# jetson_agx_breakout.net
KiCad netlist of a schematic drawn in Altium Designer
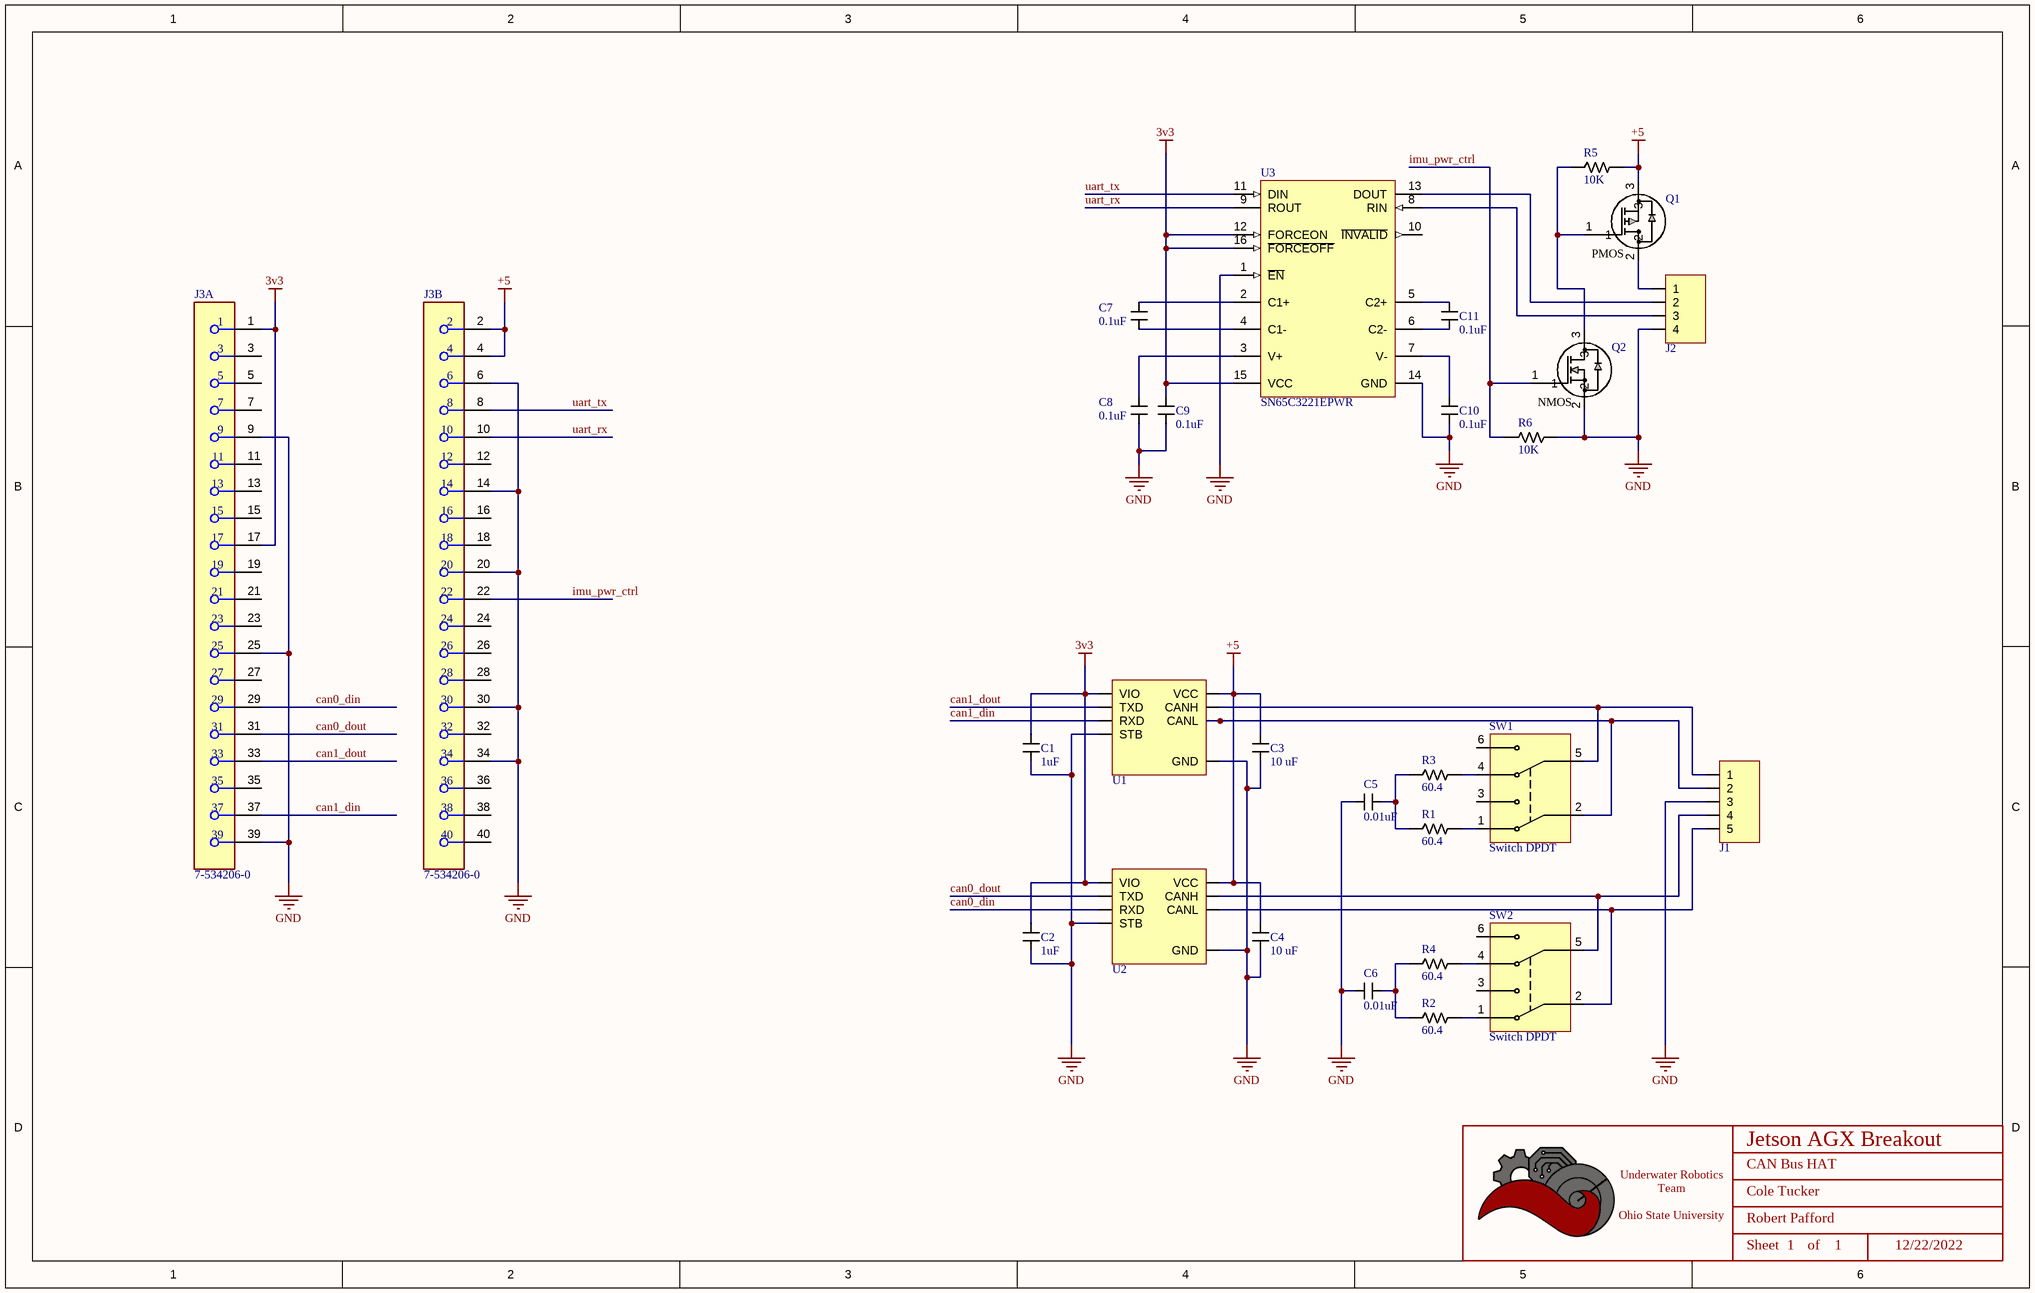
[diagram p0: jetson_agx_breakout.SchDoc]

(export (version "E")
  (design (tool "Eeschema 10.0.6"))
  (components
    (comp (ref "*")
      (value "Title_Block")
      (footprint "LOGO")
      (description "UWRT Schematic Title Block Template\r\n\r\nCreated June 2021, Dylan Trainor")
      (libsource (lib "UWRT") (part "Title_Block"))
    )
    (comp (ref "C1")
      (value "1uF")
      (footprint "CAPACITOR_0603")
      (description "Cap 1uF 16V +/-10%\r\nCeramic 0603")
      (fields
        (field (name "TOLERANCE") "+/- 10%")
        (field (name "VOLTAGE") "16V")
        (field (name "MADE BY") "Flip B")
      )
      (libsource (lib "Capacitors") (part "CAPACITOR_1uF_0603"))
    )
    (comp (ref "C2")
      (value "1uF")
      (footprint "CAPACITOR_0603")
      (description "Cap 1uF 16V +/-10%\r\nCeramic 0603")
      (fields
        (field (name "TOLERANCE") "+/- 10%")
        (field (name "VOLTAGE") "16V")
        (field (name "MADE BY") "Flip B")
      )
      (libsource (lib "Capacitors") (part "CAPACITOR_1uF_0603"))
    )
    (comp (ref "C3")
      (value "10uF Ceramic 6.3V")
      (footprint "CAPACITOR_0603")
      (description "Cap 10uF 6.3V +/-20%\r\nCeramic 0603")
      (fields
        (field (name "TOLERANCE") "+/- 20%")
        (field (name "VOLTAGE") "6.3V")
        (field (name "VALUE (UF)") "10 uF")
        (field (name "MADE BY") "Flip B")
      )
      (libsource (lib "Capacitors") (part "CAPACITOR_10uF_0603"))
    )
    (comp (ref "C4")
      (value "10uF Ceramic 6.3V")
      (footprint "CAPACITOR_0603")
      (description "Cap 10uF 6.3V +/-20%\r\nCeramic 0603")
      (fields
        (field (name "TOLERANCE") "+/- 20%")
        (field (name "VOLTAGE") "6.3V")
        (field (name "VALUE (UF)") "10 uF")
        (field (name "MADE BY") "Flip B")
      )
      (libsource (lib "Capacitors") (part "CAPACITOR_10uF_0603"))
    )
    (comp (ref "C5")
      (value "0.01uF")
      (footprint "CAPACITOR_0603")
      (description "Cap 10nF 6.3V +/-20%\r\nCeramic 0603")
      (fields
        (field (name "TOLERANCE") "+/- 10%")
        (field (name "VOLTAGE") "6.3V")
        (field (name "MADE BY") "Flip B")
      )
      (libsource (lib "Capacitors") (part "CAPACITOR_0.01uF_0603"))
    )
    (comp (ref "C6")
      (value "0.01uF")
      (footprint "CAPACITOR_0603")
      (description "Cap 10nF 6.3V +/-20%\r\nCeramic 0603")
      (fields
        (field (name "TOLERANCE") "+/- 10%")
        (field (name "VOLTAGE") "6.3V")
        (field (name "MADE BY") "Flip B")
      )
      (libsource (lib "Capacitors") (part "CAPACITOR_0.01uF_0603"))
    )
    (comp (ref "C7")
      (value "0.1uF")
      (footprint "CAPACITOR_0603")
      (description "Cap 100nF 6.3V +/-10%\r\nCeramic 0603")
      (fields
        (field (name "TOLERANCE") "+/- 10%")
        (field (name "VOLTAGE") "6.3V")
        (field (name "MADE BY") "Flip B")
      )
      (libsource (lib "Capacitors") (part "CAPACITOR_0.1uF_0603"))
    )
    (comp (ref "C8")
      (value "0.1uF")
      (footprint "CAPACITOR_0603")
      (description "Cap 100nF 6.3V +/-10%\r\nCeramic 0603")
      (fields
        (field (name "TOLERANCE") "+/- 10%")
        (field (name "VOLTAGE") "6.3V")
        (field (name "MADE BY") "Flip B")
      )
      (libsource (lib "Capacitors") (part "CAPACITOR_0.1uF_0603"))
    )
    (comp (ref "C9")
      (value "0.1uF")
      (footprint "CAPACITOR_0603")
      (description "Cap 100nF 6.3V +/-10%\r\nCeramic 0603")
      (fields
        (field (name "TOLERANCE") "+/- 10%")
        (field (name "VOLTAGE") "6.3V")
        (field (name "MADE BY") "Flip B")
      )
      (libsource (lib "Capacitors") (part "CAPACITOR_0.1uF_0603"))
    )
    (comp (ref "C10")
      (value "0.1uF")
      (footprint "CAPACITOR_0603")
      (description "Cap 100nF 6.3V +/-10%\r\nCeramic 0603")
      (fields
        (field (name "TOLERANCE") "+/- 10%")
        (field (name "VOLTAGE") "6.3V")
        (field (name "MADE BY") "Flip B")
      )
      (libsource (lib "Capacitors") (part "CAPACITOR_0.1uF_0603"))
    )
    (comp (ref "C11")
      (value "0.1uF")
      (footprint "CAPACITOR_0603")
      (description "Cap 100nF 6.3V +/-10%\r\nCeramic 0603")
      (fields
        (field (name "TOLERANCE") "+/- 10%")
        (field (name "VOLTAGE") "6.3V")
        (field (name "MADE BY") "Flip B")
      )
      (libsource (lib "Capacitors") (part "CAPACITOR_0.1uF_0603"))
    )
    (comp (ref "J1")
      (value "5 POS VERT")
      (footprint "CONN_JST_XH254_5POS_VERT")
      (description "JST XH 2.54mm Pitch 5 Pos Vertical")
      (fields (field (name "MANUFACTURER") "JST") (field (name "CREATED BY") "Robert P"))
      (libsource (lib "Connectors") (part "CONN_JST_XH254_5POS_VERT"))
    )
    (comp (ref "J2")
      (value "4 POS VERT")
      (footprint "CONN_JST_XH254_4POS_VERT")
      (description "JST XH 2.54mm Pitch 4 Pos Vertical")
      (fields (field (name "MANUFACTURER") "JST") (field (name "CREATED BY") "Robert P"))
      (libsource (lib "Connectors") (part "CONN_JST_XH254_4POS_VERT"))
    )
    (comp (ref "J3")
      (value "7-534206-0")
      (footprint "FP-7-534206-0-MFG")
      (description "CONN RCPT 40POS 0.1 GOLD PCB")
      (fields
        (field (name "MANUFACTURER") "TE Connectivity")
        (field (name "OCTOPART") "https://octopart.com/7-534206-0-te+connectivity-39516831")
      )
      (libsource (lib "Altium Content Vault") (part "7acf1c4a8db21028d11741a46a6ec78"))
    )
    (comp (ref "Q1")
      (value "MOSFET P-CHANNEL 20V 4.7A SOT23")
      (footprint "SOT-23-3")
      (description "P-Channel 20 V 4.7A (Tc) 1.56W (Tc) Surface Mount SOT-23")
      (fields
        (field (name "MANUFACTURER_PART_NUMBER") "TSM500P02CX")
        (field (name "CREATED BY") "Robert Pafford")
      )
      (libsource (lib "Transistors") (part "TSM500P02CX"))
    )
    (comp (ref "Q2")
      (value "MOSFET N-CH 30V 5.8A SOT-23-3")
      (footprint "SOT-23-3")
      (description "N-Channel 30 V 5.8A (Ta) 1.4W (Ta) Surface Mount SOT-23-3")
      (fields (field (name "MANUFACTURER _PART_NUMBER") "AO3404A") (field (name "CREATED BY") "Dylan T"))
      (libsource (lib "Transistors") (part "AO3404A"))
    )
    (comp (ref "R1")
      (value "60.4 Ohm 1% 1/16W")
      (footprint "RESISTOR_0402")
      (description "RES 60.4 OHM 1% 1/16W 0402")
      (fields
        (field (name "TOLERANCE") "+/- 1%")
        (field (name "VALUE  (OHMS)") "60.4")
        (field (name "MADE BY") "Robert Pafford")
      )
      (libsource (lib "Resistors") (part "RESISTOR_60.4_0402"))
    )
    (comp (ref "R2")
      (value "60.4 Ohm 1% 1/16W")
      (footprint "RESISTOR_0402")
      (description "RES 60.4 OHM 1% 1/16W 0402")
      (fields
        (field (name "TOLERANCE") "+/- 1%")
        (field (name "VALUE  (OHMS)") "60.4")
        (field (name "MADE BY") "Robert Pafford")
      )
      (libsource (lib "Resistors") (part "RESISTOR_60.4_0402"))
    )
    (comp (ref "R3")
      (value "60.4 Ohm 1% 1/16W")
      (footprint "RESISTOR_0402")
      (description "RES 60.4 OHM 1% 1/16W 0402")
      (fields
        (field (name "TOLERANCE") "+/- 1%")
        (field (name "VALUE  (OHMS)") "60.4")
        (field (name "MADE BY") "Robert Pafford")
      )
      (libsource (lib "Resistors") (part "RESISTOR_60.4_0402"))
    )
    (comp (ref "R4")
      (value "60.4 Ohm 1% 1/16W")
      (footprint "RESISTOR_0402")
      (description "RES 60.4 OHM 1% 1/16W 0402")
      (fields
        (field (name "TOLERANCE") "+/- 1%")
        (field (name "VALUE  (OHMS)") "60.4")
        (field (name "MADE BY") "Robert Pafford")
      )
      (libsource (lib "Resistors") (part "RESISTOR_60.4_0402"))
    )
    (comp (ref "R5")
      (value "10k Ohm 5% 1/10W")
      (footprint "RESISTOR_0603")
      (description "RES 10k OHM 5% 1/10W 0603")
      (fields
        (field (name "TOLERANCE") "+/- 5%")
        (field (name "VALUE  (OHMS)") "10K")
        (field (name "MADE BY") "Robert Pafford")
      )
      (libsource (lib "Resistors") (part "RESISTOR_10K_0603"))
    )
    (comp (ref "R6")
      (value "10k Ohm 5% 1/10W")
      (footprint "RESISTOR_0603")
      (description "RES 10k OHM 5% 1/10W 0603")
      (fields
        (field (name "TOLERANCE") "+/- 5%")
        (field (name "VALUE  (OHMS)") "10K")
        (field (name "MADE BY") "Robert Pafford")
      )
      (libsource (lib "Resistors") (part "RESISTOR_10K_0603"))
    )
    (comp (ref "SW1")
      (value "Switch DPDT")
      (footprint "CAS-220TA")
      (description "GOLD SWITCH FLUSH SLIDE DPDT 100MA 6V")
      (fields (field (name "MADE BY") "Robert Pafford"))
      (libsource (lib "Switches") (part "CAS-220TA_CAN_TERM"))
    )
    (comp (ref "SW2")
      (value "Switch DPDT")
      (footprint "CAS-220TA")
      (description "GOLD SWITCH FLUSH SLIDE DPDT 100MA 6V")
      (fields (field (name "MADE BY") "Robert Pafford"))
      (libsource (lib "Switches") (part "CAS-220TA_CAN_TERM"))
    )
    (comp (ref "U1")
      (value "CAN Transceiver")
      (footprint "SOIC-8")
      (description "CAN Interface IC High-Speed CAN Transceiver with Standby Mode")
      (fields (field (name "MADE BY") "Robert Pafford"))
      (libsource (lib "Integrated Circuits") (part "TJA1442AT"))
    )
    (comp (ref "U2")
      (value "CAN Transceiver")
      (footprint "SOIC-8")
      (description "CAN Interface IC High-Speed CAN Transceiver with Standby Mode")
      (fields (field (name "MADE BY") "Robert Pafford"))
      (libsource (lib "Integrated Circuits") (part "TJA1442AT"))
    )
    (comp (ref "U3")
      (value "SN65C3221EPWR")
      (footprint "PW0016A_M")
      (libsource (lib "Altium Content Vault") (part "TI-SN65C3221E-TSSOP_PW-16"))
    )
  )
  (nets
    (net (code "1") (name "+5") (class "Default")
      (node (ref "C3") (pin "1") (pinfunction "1_1") (pintype "passive"))
      (node (ref "C4") (pin "1") (pinfunction "1_1") (pintype "passive"))
      (node (ref "J3") (pin "2") (pinfunction "2_2") (pintype "passive"))
      (node (ref "J3") (pin "4") (pinfunction "4_4") (pintype "passive"))
      (node (ref "Q1") (pin "3") (pinfunction "3_3") (pintype "passive"))
      (node (ref "R5") (pin "1") (pinfunction "1_1") (pintype "passive"))
      (node (ref "U1") (pin "3") (pinfunction "VCC_3") (pintype "passive"))
      (node (ref "U2") (pin "3") (pinfunction "VCC_3") (pintype "passive"))
    )
    (net (code "2") (name "/can0_din") (class "Default")
      (node (ref "J3") (pin "29") (pinfunction "29_29") (pintype "passive"))
      (node (ref "U2") (pin "4") (pinfunction "RXD_4") (pintype "passive"))
    )
    (net (code "3") (name "/can0_dout") (class "Default")
      (node (ref "J3") (pin "31") (pinfunction "31_31") (pintype "passive"))
      (node (ref "U2") (pin "1") (pinfunction "TXD_1") (pintype "passive"))
    )
    (net (code "4") (name "/can1_din") (class "Default")
      (node (ref "J3") (pin "37") (pinfunction "37_37") (pintype "passive"))
      (node (ref "U1") (pin "4") (pinfunction "RXD_4") (pintype "passive"))
    )
    (net (code "5") (name "/can1_dout") (class "Default")
      (node (ref "J3") (pin "33") (pinfunction "33_33") (pintype "passive"))
      (node (ref "U1") (pin "1") (pinfunction "TXD_1") (pintype "passive"))
    )
    (net (code "6") (name "/imu_pwr_ctrl") (class "Default")
      (node (ref "J3") (pin "22") (pinfunction "22_22") (pintype "passive"))
      (node (ref "Q2") (pin "1") (pinfunction "1_1") (pintype "passive"))
      (node (ref "R6") (pin "1") (pinfunction "1_1") (pintype "passive"))
    )
    (net (code "7") (name "/uart_rx") (class "Default")
      (node (ref "J3") (pin "10") (pinfunction "10_10") (pintype "passive"))
      (node (ref "U3") (pin "9") (pinfunction "ROUT_9") (pintype "tri_state"))
    )
    (net (code "8") (name "/uart_tx") (class "Default")
      (node (ref "J3") (pin "8") (pinfunction "8_8") (pintype "passive"))
      (node (ref "U3") (pin "11") (pinfunction "DIN_11") (pintype "input"))
    )
    (net (code "9") (name "3v3") (class "Default")
      (node (ref "C1") (pin "1") (pinfunction "1_1") (pintype "passive"))
      (node (ref "C2") (pin "1") (pinfunction "1_1") (pintype "passive"))
      (node (ref "C9") (pin "1") (pinfunction "1_1") (pintype "passive"))
      (node (ref "J3") (pin "1") (pinfunction "1_1") (pintype "passive"))
      (node (ref "J3") (pin "17") (pinfunction "17_17") (pintype "passive"))
      (node (ref "U1") (pin "5") (pinfunction "VIO_5") (pintype "passive"))
      (node (ref "U2") (pin "5") (pinfunction "VIO_5") (pintype "passive"))
      (node (ref "U3") (pin "12") (pinfunction "FORCEON_12") (pintype "input"))
      (node (ref "U3") (pin "15") (pinfunction "VCC_15") (pintype "power_in"))
      (node (ref "U3") (pin "16") (pinfunction "~{FORCEOFF}_16") (pintype "input"))
    )
    (net (code "10") (name "GND") (class "Default")
      (node (ref "C1") (pin "2") (pinfunction "2_2") (pintype "passive"))
      (node (ref "C10") (pin "2") (pinfunction "2_2") (pintype "passive"))
      (node (ref "C2") (pin "2") (pinfunction "2_2") (pintype "passive"))
      (node (ref "C3") (pin "2") (pinfunction "2_2") (pintype "passive"))
      (node (ref "C4") (pin "2") (pinfunction "2_2") (pintype "passive"))
      (node (ref "C5") (pin "1") (pinfunction "1_1") (pintype "passive"))
      (node (ref "C6") (pin "1") (pinfunction "1_1") (pintype "passive"))
      (node (ref "C8") (pin "2") (pinfunction "2_2") (pintype "passive"))
      (node (ref "C9") (pin "2") (pinfunction "2_2") (pintype "passive"))
      (node (ref "J1") (pin "3") (pinfunction "3_3") (pintype "passive"))
      (node (ref "J2") (pin "4") (pinfunction "4_4") (pintype "passive"))
      (node (ref "J3") (pin "14") (pinfunction "14_14") (pintype "passive"))
      (node (ref "J3") (pin "20") (pinfunction "20_20") (pintype "passive"))
      (node (ref "J3") (pin "25") (pinfunction "25_25") (pintype "passive"))
      (node (ref "J3") (pin "30") (pinfunction "30_30") (pintype "passive"))
      (node (ref "J3") (pin "34") (pinfunction "34_34") (pintype "passive"))
      (node (ref "J3") (pin "39") (pinfunction "39_39") (pintype "passive"))
      (node (ref "J3") (pin "6") (pinfunction "6_6") (pintype "passive"))
      (node (ref "J3") (pin "9") (pinfunction "9_9") (pintype "passive"))
      (node (ref "Q2") (pin "2") (pinfunction "2_2") (pintype "passive"))
      (node (ref "R6") (pin "2") (pinfunction "2_2") (pintype "passive"))
      (node (ref "U1") (pin "2") (pinfunction "GND_2") (pintype "passive"))
      (node (ref "U1") (pin "8") (pinfunction "STB_8") (pintype "passive"))
      (node (ref "U2") (pin "2") (pinfunction "GND_2") (pintype "passive"))
      (node (ref "U2") (pin "8") (pinfunction "STB_8") (pintype "passive"))
      (node (ref "U3") (pin "1") (pinfunction "~{EN}_1") (pintype "input"))
      (node (ref "U3") (pin "14") (pinfunction "GND_14") (pintype "power_in"))
    )
    (net (code "11") (name "Net-(C5-Pad2)") (class "Default")
      (node (ref "C5") (pin "2") (pinfunction "2_2") (pintype "passive"))
      (node (ref "R1") (pin "2") (pinfunction "2_2") (pintype "passive"))
      (node (ref "R3") (pin "2") (pinfunction "2_2") (pintype "passive"))
    )
    (net (code "12") (name "Net-(C6-Pad2)") (class "Default")
      (node (ref "C6") (pin "2") (pinfunction "2_2") (pintype "passive"))
      (node (ref "R2") (pin "2") (pinfunction "2_2") (pintype "passive"))
      (node (ref "R4") (pin "2") (pinfunction "2_2") (pintype "passive"))
    )
    (net (code "13") (name "Net-(J2-Pad1)") (class "Default")
      (node (ref "J2") (pin "1") (pinfunction "1_1") (pintype "passive"))
      (node (ref "Q1") (pin "2") (pinfunction "2_2") (pintype "passive"))
    )
    (net (code "14") (name "Net-(Q1-Pad1)") (class "Default")
      (node (ref "Q1") (pin "1") (pinfunction "1_1") (pintype "passive"))
      (node (ref "Q2") (pin "3") (pinfunction "3_3") (pintype "passive"))
      (node (ref "R5") (pin "2") (pinfunction "2_2") (pintype "passive"))
    )
    (net (code "15") (name "Net-(R1-Pad1)") (class "Default")
      (node (ref "R1") (pin "1") (pinfunction "1_1") (pintype "passive"))
      (node (ref "SW1") (pin "1") (pintype "passive"))
    )
    (net (code "16") (name "Net-(R2-Pad1)") (class "Default")
      (node (ref "R2") (pin "1") (pinfunction "1_1") (pintype "passive"))
      (node (ref "SW2") (pin "1") (pintype "passive"))
    )
    (net (code "17") (name "Net-(R3-Pad1)") (class "Default")
      (node (ref "R3") (pin "1") (pinfunction "1_1") (pintype "passive"))
      (node (ref "SW1") (pin "4") (pintype "passive"))
    )
    (net (code "18") (name "Net-(R4-Pad1)") (class "Default")
      (node (ref "R4") (pin "1") (pinfunction "1_1") (pintype "passive"))
      (node (ref "SW2") (pin "4") (pintype "passive"))
    )
    (net (code "19") (name "Net-(U1-CANH)") (class "Default")
      (node (ref "J1") (pin "1") (pinfunction "1_1") (pintype "passive"))
      (node (ref "SW1") (pin "5") (pintype "passive"))
      (node (ref "U1") (pin "7") (pinfunction "CANH_7") (pintype "passive"))
    )
    (net (code "20") (name "Net-(U1-CANL)") (class "Default")
      (node (ref "J1") (pin "2") (pinfunction "2_2") (pintype "passive"))
      (node (ref "SW1") (pin "2") (pintype "passive"))
      (node (ref "U1") (pin "6") (pinfunction "CANL_6") (pintype "passive"))
    )
    (net (code "21") (name "Net-(U2-CANH)") (class "Default")
      (node (ref "J1") (pin "4") (pinfunction "4_4") (pintype "passive"))
      (node (ref "SW2") (pin "5") (pintype "passive"))
      (node (ref "U2") (pin "7") (pinfunction "CANH_7") (pintype "passive"))
    )
    (net (code "22") (name "Net-(U2-CANL)") (class "Default")
      (node (ref "J1") (pin "5") (pinfunction "5_5") (pintype "passive"))
      (node (ref "SW2") (pin "2") (pintype "passive"))
      (node (ref "U2") (pin "6") (pinfunction "CANL_6") (pintype "passive"))
    )
    (net (code "23") (name "Net-(U3-C1+)") (class "Default")
      (node (ref "C7") (pin "1") (pinfunction "1_1") (pintype "passive"))
      (node (ref "U3") (pin "2") (pinfunction "C1+_2") (pintype "passive"))
    )
    (net (code "24") (name "Net-(U3-C1-)") (class "Default")
      (node (ref "C7") (pin "2") (pinfunction "2_2") (pintype "passive"))
      (node (ref "U3") (pin "4") (pinfunction "C1-_4") (pintype "passive"))
    )
    (net (code "25") (name "Net-(U3-C2+)") (class "Default")
      (node (ref "C11") (pin "1") (pinfunction "1_1") (pintype "passive"))
      (node (ref "U3") (pin "5") (pinfunction "C2+_5") (pintype "passive"))
    )
    (net (code "26") (name "Net-(U3-C2-)") (class "Default")
      (node (ref "C11") (pin "2") (pinfunction "2_2") (pintype "passive"))
      (node (ref "U3") (pin "6") (pinfunction "C2-_6") (pintype "passive"))
    )
    (net (code "27") (name "Net-(U3-DOUT)") (class "Default")
      (node (ref "J2") (pin "2") (pinfunction "2_2") (pintype "passive"))
      (node (ref "U3") (pin "13") (pinfunction "DOUT_13") (pintype "tri_state"))
    )
    (net (code "28") (name "Net-(U3-RIN)") (class "Default")
      (node (ref "J2") (pin "3") (pinfunction "3_3") (pintype "passive"))
      (node (ref "U3") (pin "8") (pinfunction "RIN_8") (pintype "input"))
    )
    (net (code "29") (name "Net-(U3-V+)") (class "Default")
      (node (ref "C8") (pin "1") (pinfunction "1_1") (pintype "passive"))
      (node (ref "U3") (pin "3") (pinfunction "V+_3") (pintype "power_in"))
    )
    (net (code "30") (name "Net-(U3-V-)") (class "Default")
      (node (ref "C10") (pin "1") (pinfunction "1_1") (pintype "passive"))
      (node (ref "U3") (pin "7") (pinfunction "V-_7") (pintype "power_in"))
    )
    (net (code "31") (name "unconnected-(J3-Pad3)") (class "Default")
      (node (ref "J3") (pin "3") (pinfunction "3_3") (pintype "passive"))
    )
    (net (code "32") (name "unconnected-(J3-Pad5)") (class "Default")
      (node (ref "J3") (pin "5") (pinfunction "5_5") (pintype "passive"))
    )
    (net (code "33") (name "unconnected-(J3-Pad7)") (class "Default")
      (node (ref "J3") (pin "7") (pinfunction "7_7") (pintype "passive"))
    )
    (net (code "34") (name "unconnected-(J3-Pad11)") (class "Default")
      (node (ref "J3") (pin "11") (pinfunction "11_11") (pintype "passive"))
    )
    (net (code "35") (name "unconnected-(J3-Pad12)") (class "Default")
      (node (ref "J3") (pin "12") (pinfunction "12_12") (pintype "passive"))
    )
    (net (code "36") (name "unconnected-(J3-Pad13)") (class "Default")
      (node (ref "J3") (pin "13") (pinfunction "13_13") (pintype "passive"))
    )
    (net (code "37") (name "unconnected-(J3-Pad15)") (class "Default")
      (node (ref "J3") (pin "15") (pinfunction "15_15") (pintype "passive"))
    )
    (net (code "38") (name "unconnected-(J3-Pad16)") (class "Default")
      (node (ref "J3") (pin "16") (pinfunction "16_16") (pintype "passive"))
    )
    (net (code "39") (name "unconnected-(J3-Pad18)") (class "Default")
      (node (ref "J3") (pin "18") (pinfunction "18_18") (pintype "passive"))
    )
    (net (code "40") (name "unconnected-(J3-Pad19)") (class "Default")
      (node (ref "J3") (pin "19") (pinfunction "19_19") (pintype "passive"))
    )
    (net (code "41") (name "unconnected-(J3-Pad21)") (class "Default")
      (node (ref "J3") (pin "21") (pinfunction "21_21") (pintype "passive"))
    )
    (net (code "42") (name "unconnected-(J3-Pad23)") (class "Default")
      (node (ref "J3") (pin "23") (pinfunction "23_23") (pintype "passive"))
    )
    (net (code "43") (name "unconnected-(J3-Pad24)") (class "Default")
      (node (ref "J3") (pin "24") (pinfunction "24_24") (pintype "passive"))
    )
    (net (code "44") (name "unconnected-(J3-Pad26)") (class "Default")
      (node (ref "J3") (pin "26") (pinfunction "26_26") (pintype "passive"))
    )
    (net (code "45") (name "unconnected-(J3-Pad27)") (class "Default")
      (node (ref "J3") (pin "27") (pinfunction "27_27") (pintype "passive"))
    )
    (net (code "46") (name "unconnected-(J3-Pad28)") (class "Default")
      (node (ref "J3") (pin "28") (pinfunction "28_28") (pintype "passive"))
    )
    (net (code "47") (name "unconnected-(J3-Pad32)") (class "Default")
      (node (ref "J3") (pin "32") (pinfunction "32_32") (pintype "passive"))
    )
    (net (code "48") (name "unconnected-(J3-Pad35)") (class "Default")
      (node (ref "J3") (pin "35") (pinfunction "35_35") (pintype "passive"))
    )
    (net (code "49") (name "unconnected-(J3-Pad36)") (class "Default")
      (node (ref "J3") (pin "36") (pinfunction "36_36") (pintype "passive"))
    )
    (net (code "50") (name "unconnected-(J3-Pad38)") (class "Default")
      (node (ref "J3") (pin "38") (pinfunction "38_38") (pintype "passive"))
    )
    (net (code "51") (name "unconnected-(J3-Pad40)") (class "Default")
      (node (ref "J3") (pin "40") (pinfunction "40_40") (pintype "passive"))
    )
    (net (code "52") (name "unconnected-(SW1-Pad3)") (class "Default")
      (node (ref "SW1") (pin "3") (pintype "passive"))
    )
    (net (code "53") (name "unconnected-(SW1-Pad6)") (class "Default")
      (node (ref "SW1") (pin "6") (pintype "passive"))
    )
    (net (code "54") (name "unconnected-(SW2-Pad3)") (class "Default")
      (node (ref "SW2") (pin "3") (pintype "passive"))
    )
    (net (code "55") (name "unconnected-(SW2-Pad6)") (class "Default")
      (node (ref "SW2") (pin "6") (pintype "passive"))
    )
    (net (code "56") (name "unconnected-(U3-~{INVALID}-Pad10)") (class "Default")
      (node (ref "U3") (pin "10") (pinfunction "~{INVALID}_10") (pintype "output"))
    )
  )
)
